# preamp.net
KiCad netlist of a schematic drawn in EAGLE
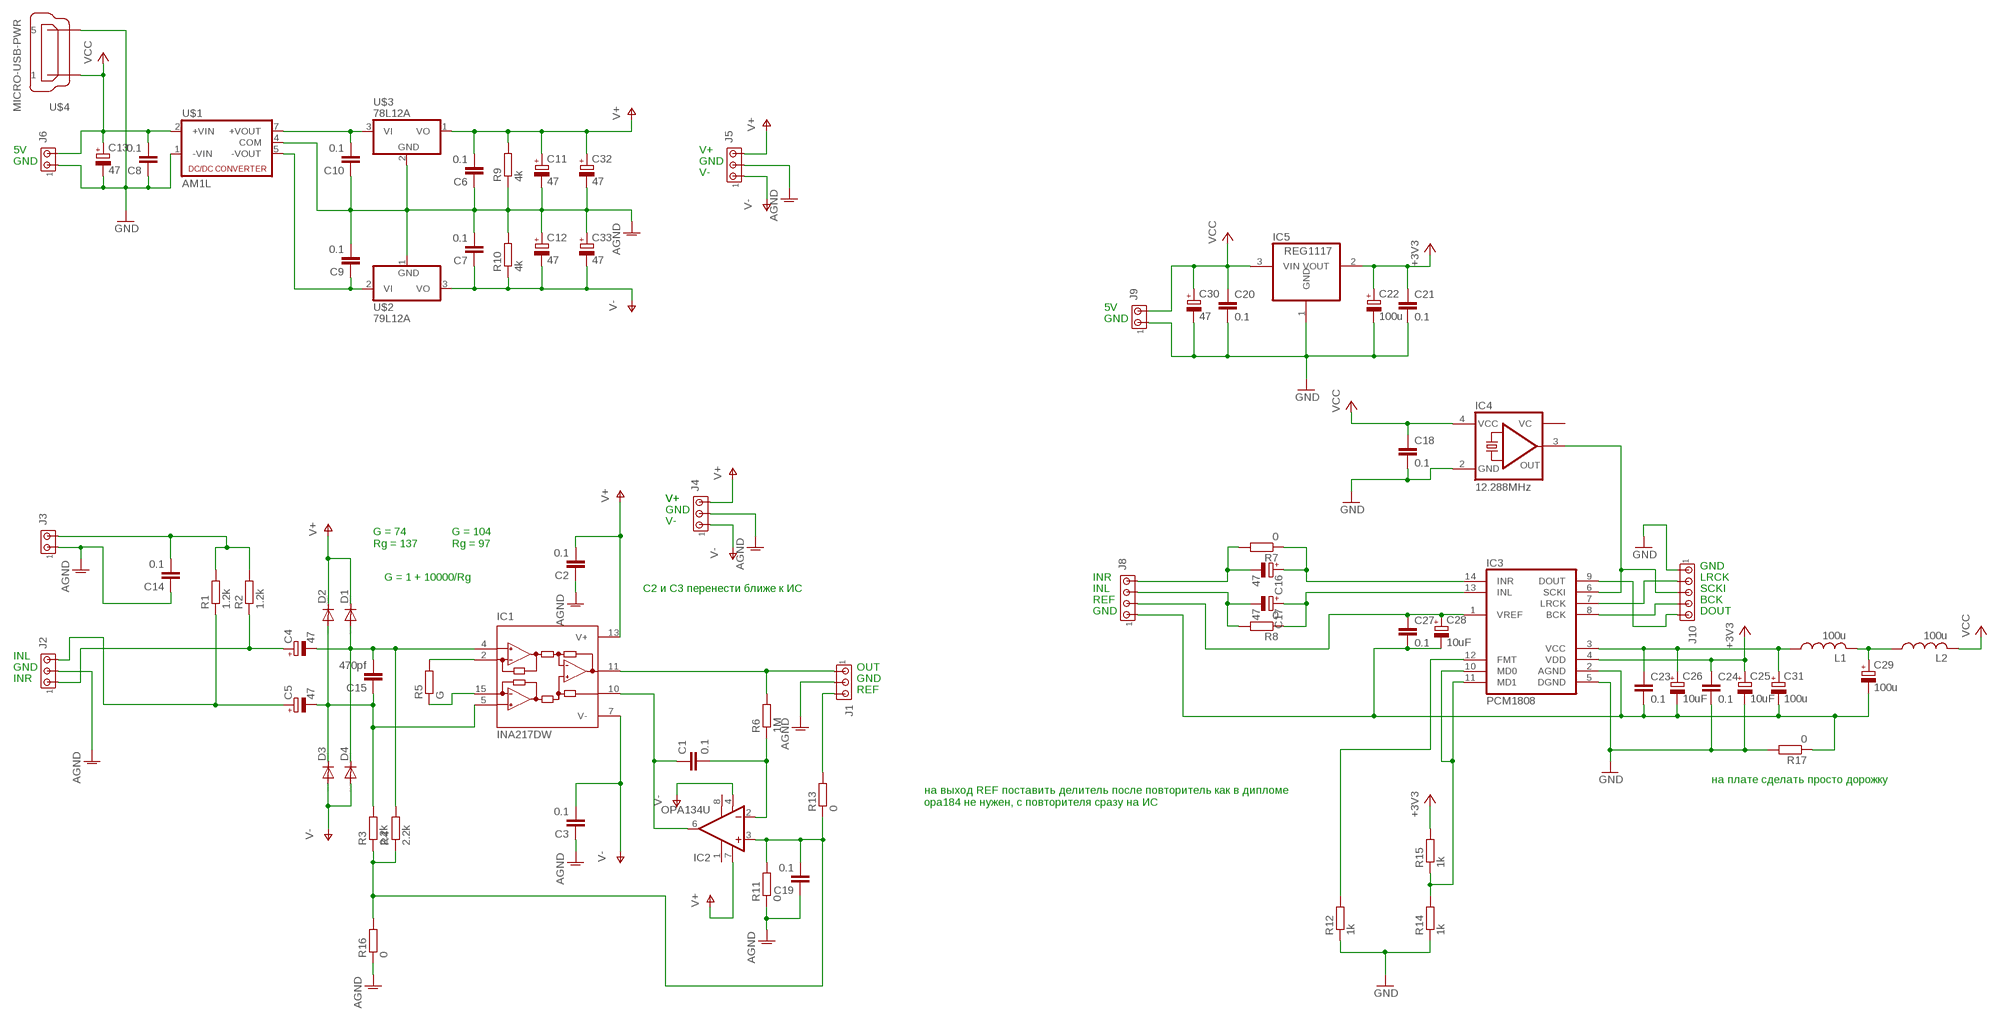
[diagram p0: schematic, sheet 1]

(export (version "E")
  (design (tool "Eeschema 10.0.6"))
  (components
    (comp (ref "C1")
      (value "0.1")
      (footprint "eagle-import:C0805")
      (libsource (lib "eagle-import") (part "C-EUC0805"))
    )
    (comp (ref "C2")
      (value "0.1")
      (footprint "eagle-import:C0805")
      (libsource (lib "eagle-import") (part "C-EUC0805"))
    )
    (comp (ref "C3")
      (value "0.1")
      (footprint "eagle-import:C0805")
      (libsource (lib "eagle-import") (part "C-EUC0805"))
    )
    (comp (ref "C4")
      (value "47")
      (footprint "eagle-import:153CLV-0605")
      (libsource (lib "eagle-import") (part "CPOL-EU153CLV-0605"))
    )
    (comp (ref "C5")
      (value "47")
      (footprint "eagle-import:153CLV-0605")
      (libsource (lib "eagle-import") (part "CPOL-EU153CLV-0605"))
    )
    (comp (ref "C6")
      (value "0.1")
      (footprint "eagle-import:C0805")
      (libsource (lib "eagle-import") (part "C-EUC0805"))
    )
    (comp (ref "C7")
      (value "0.1")
      (footprint "eagle-import:C0805")
      (libsource (lib "eagle-import") (part "C-EUC0805"))
    )
    (comp (ref "C8")
      (value "0.1")
      (footprint "eagle-import:C0805")
      (libsource (lib "eagle-import") (part "C-EUC0805"))
    )
    (comp (ref "C9")
      (value "0.1")
      (footprint "eagle-import:C0805")
      (libsource (lib "eagle-import") (part "C-EUC0805"))
    )
    (comp (ref "C10")
      (value "0.1")
      (footprint "eagle-import:C0805")
      (libsource (lib "eagle-import") (part "C-EUC0805"))
    )
    (comp (ref "C11")
      (value "47")
      (footprint "eagle-import:153CLV-0605")
      (libsource (lib "eagle-import") (part "CPOL-EU153CLV-0605"))
    )
    (comp (ref "C12")
      (value "47")
      (footprint "eagle-import:153CLV-0605")
      (libsource (lib "eagle-import") (part "CPOL-EU153CLV-0605"))
    )
    (comp (ref "C13")
      (value "47")
      (footprint "eagle-import:153CLV-0605")
      (libsource (lib "eagle-import") (part "CPOL-EU153CLV-0605"))
    )
    (comp (ref "C14")
      (value "0.1")
      (footprint "eagle-import:C0805")
      (libsource (lib "eagle-import") (part "C-EUC0805"))
    )
    (comp (ref "C15")
      (value "470pf")
      (footprint "eagle-import:C0805")
      (libsource (lib "eagle-import") (part "C-EUC0805"))
    )
    (comp (ref "C16")
      (value "47")
      (footprint "eagle-import:153CLV-0605")
      (libsource (lib "eagle-import") (part "CPOL-EU153CLV-0605"))
    )
    (comp (ref "C17")
      (value "47")
      (footprint "eagle-import:153CLV-0605")
      (libsource (lib "eagle-import") (part "CPOL-EU153CLV-0605"))
    )
    (comp (ref "C18")
      (value "0.1")
      (footprint "eagle-import:C0805")
      (libsource (lib "eagle-import") (part "C-EUC0805"))
    )
    (comp (ref "C19")
      (value "0.1")
      (footprint "eagle-import:C0805")
      (libsource (lib "eagle-import") (part "C-EUC0805"))
    )
    (comp (ref "C20")
      (value "0.1")
      (footprint "eagle-import:C0805")
      (libsource (lib "eagle-import") (part "C-EUC0805"))
    )
    (comp (ref "C21")
      (value "0.1")
      (footprint "eagle-import:C0805")
      (libsource (lib "eagle-import") (part "C-EUC0805"))
    )
    (comp (ref "C22")
      (value "100u")
      (footprint "eagle-import:153CLV-0605")
      (libsource (lib "eagle-import") (part "CPOL-EU153CLV-0605"))
    )
    (comp (ref "C23")
      (value "0.1")
      (footprint "eagle-import:C0805")
      (libsource (lib "eagle-import") (part "C-EUC0805"))
    )
    (comp (ref "C24")
      (value "0.1")
      (footprint "eagle-import:C0805")
      (libsource (lib "eagle-import") (part "C-EUC0805"))
    )
    (comp (ref "C25")
      (value "10uF")
      (footprint "eagle-import:SMC_A")
      (libsource (lib "eagle-import") (part "CPOL-EUSMCA"))
    )
    (comp (ref "C26")
      (value "10uF")
      (footprint "eagle-import:SMC_A")
      (libsource (lib "eagle-import") (part "CPOL-EUSMCA"))
    )
    (comp (ref "C27")
      (value "0.1")
      (footprint "eagle-import:C0805")
      (libsource (lib "eagle-import") (part "C-EUC0805"))
    )
    (comp (ref "C28")
      (value "10uF")
      (footprint "eagle-import:SMC_A")
      (libsource (lib "eagle-import") (part "CPOL-EUSMCA"))
    )
    (comp (ref "C29")
      (value "100u")
      (footprint "eagle-import:153CLV-0605")
      (libsource (lib "eagle-import") (part "CPOL-EU153CLV-0605"))
    )
    (comp (ref "C30")
      (value "47")
      (footprint "eagle-import:153CLV-0605")
      (libsource (lib "eagle-import") (part "CPOL-EU153CLV-0605"))
    )
    (comp (ref "C31")
      (value "100u")
      (footprint "eagle-import:153CLV-0605")
      (libsource (lib "eagle-import") (part "CPOL-EU153CLV-0605"))
    )
    (comp (ref "C32")
      (value "47")
      (footprint "eagle-import:153CLV-0605")
      (libsource (lib "eagle-import") (part "CPOL-EU153CLV-0605"))
    )
    (comp (ref "C33")
      (value "47")
      (footprint "eagle-import:153CLV-0605")
      (libsource (lib "eagle-import") (part "CPOL-EU153CLV-0605"))
    )
    (comp (ref "D1")
      (value "DIODE-SOD123")
      (footprint "eagle-import:SOD123")
      (libsource (lib "eagle-import") (part "DIODE-SOD123"))
    )
    (comp (ref "D2")
      (value "DIODE-SOD123")
      (footprint "eagle-import:SOD123")
      (libsource (lib "eagle-import") (part "DIODE-SOD123"))
    )
    (comp (ref "D3")
      (value "DIODE-SOD123")
      (footprint "eagle-import:SOD123")
      (libsource (lib "eagle-import") (part "DIODE-SOD123"))
    )
    (comp (ref "D4")
      (value "DIODE-SOD123")
      (footprint "eagle-import:SOD123")
      (libsource (lib "eagle-import") (part "DIODE-SOD123"))
    )
    (comp (ref "IC1")
      (value "INA217DW")
      (footprint "eagle-import:DW_RPDSO-G16")
      (fields (field (name "MF") "TEXAS INSTRUMENTS") (field (name "MPN") "INA217AIDWT"))
      (libsource (lib "eagle-import") (part "INA217DW"))
    )
    (comp (ref "IC2")
      (value "OPA134U")
      (footprint "eagle-import:SO08")
      (fields (field (name "MF") "TEXAS INSTRUMENTS") (field (name "MPN") "OPA134UA"))
      (libsource (lib "eagle-import") (part "OPA134U"))
    )
    (comp (ref "IC3")
      (value "PCM1808")
      (footprint "eagle-import:TSSOP14")
      (libsource (lib "eagle-import") (part "PCM1808"))
    )
    (comp (ref "IC4")
      (value "12.288MHz")
      (footprint "eagle-import:KXO-97")
      (libsource (lib "eagle-import") (part "KXO-97"))
    )
    (comp (ref "IC5")
      (value "REG1117")
      (footprint "eagle-import:SOT223")
      (libsource (lib "eagle-import") (part "REG1117"))
    )
    (comp (ref "J1")
      (value "MTA03-100")
      (footprint "eagle-import:10X03MTA")
      (libsource (lib "eagle-import") (part "MTA03-100"))
    )
    (comp (ref "J2")
      (value "MTA03-100")
      (footprint "eagle-import:10X03MTA")
      (libsource (lib "eagle-import") (part "MTA03-100"))
    )
    (comp (ref "J3")
      (value "MTA02-100")
      (footprint "eagle-import:10X02MTA")
      (libsource (lib "eagle-import") (part "MTA02-100"))
    )
    (comp (ref "J4")
      (value "MTA03-100")
      (footprint "eagle-import:10X03MTA")
      (libsource (lib "eagle-import") (part "MTA03-100"))
    )
    (comp (ref "J5")
      (value "MTA03-100")
      (footprint "eagle-import:10X03MTA")
      (libsource (lib "eagle-import") (part "MTA03-100"))
    )
    (comp (ref "J6")
      (value "MTA02-100")
      (footprint "eagle-import:10X02MTA")
      (libsource (lib "eagle-import") (part "MTA02-100"))
    )
    (comp (ref "J8")
      (value "MTA04-100")
      (footprint "eagle-import:10X04MTA")
      (libsource (lib "eagle-import") (part "MTA04-100"))
    )
    (comp (ref "J9")
      (value "MTA02-100")
      (footprint "eagle-import:10X02MTA")
      (libsource (lib "eagle-import") (part "MTA02-100"))
    )
    (comp (ref "J10")
      (value "MTA05-100")
      (footprint "eagle-import:10X05MTA")
      (libsource (lib "eagle-import") (part "MTA05-100"))
    )
    (comp (ref "L1")
      (value "100u")
      (footprint "eagle-import:L3225M")
      (libsource (lib "eagle-import") (part "L-USL3225M"))
    )
    (comp (ref "L2")
      (value "100u")
      (footprint "eagle-import:L3225M")
      (libsource (lib "eagle-import") (part "L-USL3225M"))
    )
    (comp (ref "R1")
      (value "1.2k")
      (footprint "eagle-import:R0805")
      (libsource (lib "eagle-import") (part "R-EU_R0805"))
    )
    (comp (ref "R2")
      (value "1.2k")
      (footprint "eagle-import:R0805")
      (libsource (lib "eagle-import") (part "R-EU_R0805"))
    )
    (comp (ref "R3")
      (value "2.2k")
      (footprint "eagle-import:R0805")
      (libsource (lib "eagle-import") (part "R-EU_R0805"))
    )
    (comp (ref "R4")
      (value "2.2k")
      (footprint "eagle-import:R0805")
      (libsource (lib "eagle-import") (part "R-EU_R0805"))
    )
    (comp (ref "R5")
      (value "G")
      (footprint "eagle-import:R0805")
      (libsource (lib "eagle-import") (part "R-EU_R0805"))
    )
    (comp (ref "R6")
      (value "1M")
      (footprint "eagle-import:R0805")
      (libsource (lib "eagle-import") (part "R-EU_R0805"))
    )
    (comp (ref "R7")
      (value "0")
      (footprint "eagle-import:R0805")
      (libsource (lib "eagle-import") (part "R-EU_R0805"))
    )
    (comp (ref "R8")
      (value "0")
      (footprint "eagle-import:R0805")
      (libsource (lib "eagle-import") (part "R-EU_R0805"))
    )
    (comp (ref "R9")
      (value "4k")
      (footprint "eagle-import:R0805")
      (libsource (lib "eagle-import") (part "R-EU_R0805"))
    )
    (comp (ref "R10")
      (value "4k")
      (footprint "eagle-import:R0805")
      (libsource (lib "eagle-import") (part "R-EU_R0805"))
    )
    (comp (ref "R11")
      (value "0")
      (footprint "eagle-import:R0805")
      (libsource (lib "eagle-import") (part "R-EU_R0805"))
    )
    (comp (ref "R12")
      (value "1k")
      (footprint "eagle-import:R0805")
      (libsource (lib "eagle-import") (part "R-EU_R0805"))
    )
    (comp (ref "R13")
      (value "0")
      (footprint "eagle-import:R0805")
      (libsource (lib "eagle-import") (part "R-EU_R0805"))
    )
    (comp (ref "R14")
      (value "1k")
      (footprint "eagle-import:R0805")
      (libsource (lib "eagle-import") (part "R-EU_R0805"))
    )
    (comp (ref "R15")
      (value "1k")
      (footprint "eagle-import:R0805")
      (libsource (lib "eagle-import") (part "R-EU_R0805"))
    )
    (comp (ref "R16")
      (value "0")
      (footprint "eagle-import:R0805")
      (libsource (lib "eagle-import") (part "R-EU_R0805"))
    )
    (comp (ref "R17")
      (value "0")
      (footprint "eagle-import:R0805")
      (libsource (lib "eagle-import") (part "R-EU_R0805"))
    )
    (comp (ref "U$1")
      (value "AM1L")
      (footprint "eagle-import:SO20")
      (libsource (lib "eagle-import") (part "AM1L"))
    )
    (comp (ref "U$2")
      (value "79L12A")
      (footprint "eagle-import:SOT89")
      (libsource (lib "eagle-import") (part "79L12A"))
    )
    (comp (ref "U$3")
      (value "78L12A")
      (footprint "eagle-import:SOT89")
      (libsource (lib "eagle-import") (part "78L12A"))
    )
    (comp (ref "U$4")
      (value "MICRO-USB-PWR")
      (footprint "eagle-import:MICRO-USB")
      (libsource (lib "eagle-import") (part "MICRO-USB-PWR"))
    )
  )
  (nets
    (net (code "1") (name "+3V3") (class "Default")
      (node (ref "C21") (pin "1") (pinfunction "1_1") (pintype "passive"))
      (node (ref "C22") (pin "+") (pinfunction "+_+") (pintype "passive"))
      (node (ref "C24") (pin "1") (pinfunction "1_1") (pintype "passive"))
      (node (ref "C25") (pin "+") (pinfunction "+_+") (pintype "passive"))
      (node (ref "IC3") (pin "4") (pinfunction "VDD_4") (pintype "power_in"))
      (node (ref "IC5") (pin "2") (pinfunction "VOUT_2") (pintype "output"))
      (node (ref "R15") (pin "2") (pinfunction "2_2") (pintype "passive"))
    )
    (net (code "2") (name "AGND") (class "Default")
      (node (ref "C10") (pin "1") (pinfunction "1_1") (pintype "passive"))
      (node (ref "C11") (pin "-") (pinfunction "-_-") (pintype "passive"))
      (node (ref "C12") (pin "+") (pinfunction "+_+") (pintype "passive"))
      (node (ref "C14") (pin "1") (pinfunction "1_1") (pintype "passive"))
      (node (ref "C19") (pin "1") (pinfunction "1_1") (pintype "passive"))
      (node (ref "C2") (pin "1") (pinfunction "1_1") (pintype "passive"))
      (node (ref "C3") (pin "1") (pinfunction "1_1") (pintype "passive"))
      (node (ref "C32") (pin "-") (pinfunction "-_-") (pintype "passive"))
      (node (ref "C33") (pin "+") (pinfunction "+_+") (pintype "passive"))
      (node (ref "C6") (pin "1") (pinfunction "1_1") (pintype "passive"))
      (node (ref "C7") (pin "2") (pinfunction "2_2") (pintype "passive"))
      (node (ref "C9") (pin "2") (pinfunction "2_2") (pintype "passive"))
      (node (ref "J1") (pin "2") (pinfunction "2_2") (pintype "passive"))
      (node (ref "J2") (pin "2") (pinfunction "2_2") (pintype "passive"))
      (node (ref "J3") (pin "1") (pinfunction "1_1") (pintype "passive"))
      (node (ref "J4") (pin "2") (pinfunction "2_2") (pintype "passive"))
      (node (ref "J5") (pin "2") (pinfunction "2_2") (pintype "passive"))
      (node (ref "R10") (pin "2") (pinfunction "2_2") (pintype "passive"))
      (node (ref "R11") (pin "1") (pinfunction "1_1") (pintype "passive"))
      (node (ref "R16") (pin "1") (pinfunction "1_1") (pintype "passive"))
      (node (ref "R9") (pin "1") (pinfunction "1_1") (pintype "passive"))
      (node (ref "U$1") (pin "4") (pinfunction "COM_4") (pintype "passive"))
      (node (ref "U$2") (pin "1") (pinfunction "GND_1") (pintype "passive"))
      (node (ref "U$3") (pin "2") (pinfunction "GND_2") (pintype "passive"))
    )
    (net (code "3") (name "GND") (class "Default")
      (node (ref "C13") (pin "-") (pinfunction "-_-") (pintype "passive"))
      (node (ref "C18") (pin "2") (pinfunction "2_2") (pintype "passive"))
      (node (ref "C20") (pin "2") (pinfunction "2_2") (pintype "passive"))
      (node (ref "C21") (pin "2") (pinfunction "2_2") (pintype "passive"))
      (node (ref "C22") (pin "-") (pinfunction "-_-") (pintype "passive"))
      (node (ref "C24") (pin "2") (pinfunction "2_2") (pintype "passive"))
      (node (ref "C25") (pin "-") (pinfunction "-_-") (pintype "passive"))
      (node (ref "C30") (pin "-") (pinfunction "-_-") (pintype "passive"))
      (node (ref "C8") (pin "1") (pinfunction "1_1") (pintype "passive"))
      (node (ref "IC3") (pin "5") (pinfunction "DGND_5") (pintype "power_in"))
      (node (ref "IC4") (pin "2") (pinfunction "GND_2") (pintype "power_in"))
      (node (ref "IC5") (pin "1") (pinfunction "GND_1") (pintype "power_in"))
      (node (ref "J10") (pin "1") (pinfunction "1_1") (pintype "passive"))
      (node (ref "J6") (pin "1") (pinfunction "1_1") (pintype "passive"))
      (node (ref "J9") (pin "1") (pinfunction "1_1") (pintype "passive"))
      (node (ref "R12") (pin "1") (pinfunction "1_1") (pintype "passive"))
      (node (ref "R14") (pin "1") (pinfunction "1_1") (pintype "passive"))
      (node (ref "R17") (pin "2") (pinfunction "2_2") (pintype "passive"))
      (node (ref "U$1") (pin "1") (pinfunction "-VIN_1") (pintype "passive"))
      (node (ref "U$4") (pin "5") (pinfunction "5_5") (pintype "passive"))
    )
    (net (code "4") (name "Net-(C4-Pad+)") (class "Default")
      (node (ref "C4") (pin "+") (pinfunction "+_+") (pintype "passive"))
      (node (ref "J2") (pin "1") (pinfunction "1_1") (pintype "passive"))
      (node (ref "R2") (pin "1") (pinfunction "1_1") (pintype "passive"))
    )
    (net (code "5") (name "Net-(C5-Pad+)") (class "Default")
      (node (ref "C5") (pin "+") (pinfunction "+_+") (pintype "passive"))
      (node (ref "J2") (pin "3") (pinfunction "3_3") (pintype "passive"))
      (node (ref "R1") (pin "1") (pinfunction "1_1") (pintype "passive"))
    )
    (net (code "6") (name "Net-(C14-Pad2)") (class "Default")
      (node (ref "C14") (pin "2") (pinfunction "2_2") (pintype "passive"))
      (node (ref "J3") (pin "2") (pinfunction "2_2") (pintype "passive"))
      (node (ref "R1") (pin "2") (pinfunction "2_2") (pintype "passive"))
      (node (ref "R2") (pin "2") (pinfunction "2_2") (pintype "passive"))
    )
    (net (code "7") (name "Net-(C16-Pad-)") (class "Default")
      (node (ref "C16") (pin "-") (pinfunction "-_-") (pintype "passive"))
      (node (ref "J8") (pin "4") (pinfunction "4_4") (pintype "passive"))
      (node (ref "R7") (pin "2") (pinfunction "2_2") (pintype "passive"))
    )
    (net (code "8") (name "Net-(C17-Pad-)") (class "Default")
      (node (ref "C17") (pin "-") (pinfunction "-_-") (pintype "passive"))
      (node (ref "J8") (pin "3") (pinfunction "3_3") (pintype "passive"))
      (node (ref "R8") (pin "2") (pinfunction "2_2") (pintype "passive"))
    )
    (net (code "9") (name "Net-(C29-Pad+)") (class "Default")
      (node (ref "C29") (pin "+") (pinfunction "+_+") (pintype "passive"))
      (node (ref "L1") (pin "2") (pinfunction "2_2") (pintype "passive"))
      (node (ref "L2") (pin "1") (pinfunction "1_1") (pintype "passive"))
    )
    (net (code "10") (name "Net-(IC1-+IN)") (class "Default")
      (node (ref "C15") (pin "1") (pinfunction "1_1") (pintype "passive"))
      (node (ref "C5") (pin "-") (pinfunction "-_-") (pintype "passive"))
      (node (ref "D2") (pin "A") (pinfunction "A_A") (pintype "passive"))
      (node (ref "D3") (pin "C") (pinfunction "C_C") (pintype "passive"))
      (node (ref "IC1") (pin "5") (pinfunction "+IN_5") (pintype "input"))
      (node (ref "R3") (pin "2") (pinfunction "2_2") (pintype "passive"))
    )
    (net (code "11") (name "Net-(IC1--IN)") (class "Default")
      (node (ref "C15") (pin "2") (pinfunction "2_2") (pintype "passive"))
      (node (ref "C4") (pin "-") (pinfunction "-_-") (pintype "passive"))
      (node (ref "D1") (pin "A") (pinfunction "A_A") (pintype "passive"))
      (node (ref "D4") (pin "C") (pinfunction "C_C") (pintype "passive"))
      (node (ref "IC1") (pin "4") (pinfunction "-IN_4") (pintype "input"))
      (node (ref "R4") (pin "2") (pinfunction "2_2") (pintype "passive"))
    )
    (net (code "12") (name "Net-(IC1-OUT)") (class "Default")
      (node (ref "IC1") (pin "11") (pinfunction "OUT_11") (pintype "output"))
      (node (ref "J1") (pin "1") (pinfunction "1_1") (pintype "passive"))
      (node (ref "R6") (pin "2") (pinfunction "2_2") (pintype "passive"))
    )
    (net (code "13") (name "Net-(IC1-REF)") (class "Default")
      (node (ref "C1") (pin "1") (pinfunction "1_1") (pintype "passive"))
      (node (ref "IC1") (pin "10") (pinfunction "REF_10") (pintype "passive"))
      (node (ref "IC2") (pin "6") (pinfunction "OUT_6") (pintype "output"))
    )
    (net (code "14") (name "Net-(IC1-RG1)") (class "Default")
      (node (ref "IC1") (pin "2") (pinfunction "RG1_2") (pintype "passive"))
      (node (ref "R5") (pin "2") (pinfunction "2_2") (pintype "passive"))
    )
    (net (code "15") (name "Net-(IC1-RG2)") (class "Default")
      (node (ref "IC1") (pin "15") (pinfunction "RG2_15") (pintype "passive"))
      (node (ref "R5") (pin "1") (pinfunction "1_1") (pintype "passive"))
    )
    (net (code "16") (name "Net-(IC2-+IN)") (class "Default")
      (node (ref "C19") (pin "2") (pinfunction "2_2") (pintype "passive"))
      (node (ref "IC2") (pin "3") (pinfunction "+IN_3") (pintype "input"))
      (node (ref "R11") (pin "2") (pinfunction "2_2") (pintype "passive"))
      (node (ref "R13") (pin "1") (pinfunction "1_1") (pintype "passive"))
      (node (ref "R16") (pin "2") (pinfunction "2_2") (pintype "passive"))
      (node (ref "R3") (pin "1") (pinfunction "1_1") (pintype "passive"))
      (node (ref "R4") (pin "1") (pinfunction "1_1") (pintype "passive"))
    )
    (net (code "17") (name "Net-(IC2--IN)") (class "Default")
      (node (ref "C1") (pin "2") (pinfunction "2_2") (pintype "passive"))
      (node (ref "IC2") (pin "2") (pinfunction "-IN_2") (pintype "input"))
      (node (ref "R6") (pin "1") (pinfunction "1_1") (pintype "passive"))
    )
    (net (code "18") (name "Net-(IC3-AGND)") (class "Default")
      (node (ref "C23") (pin "2") (pinfunction "2_2") (pintype "passive"))
      (node (ref "C26") (pin "-") (pinfunction "-_-") (pintype "passive"))
      (node (ref "C27") (pin "2") (pinfunction "2_2") (pintype "passive"))
      (node (ref "C28") (pin "-") (pinfunction "-_-") (pintype "passive"))
      (node (ref "C29") (pin "-") (pinfunction "-_-") (pintype "passive"))
      (node (ref "C31") (pin "-") (pinfunction "-_-") (pintype "passive"))
      (node (ref "IC3") (pin "2") (pinfunction "AGND_2") (pintype "power_in"))
      (node (ref "J8") (pin "1") (pinfunction "1_1") (pintype "passive"))
      (node (ref "R17") (pin "1") (pinfunction "1_1") (pintype "passive"))
    )
    (net (code "19") (name "Net-(IC3-BCK)") (class "Default")
      (node (ref "IC3") (pin "8") (pinfunction "BCK_8") (pintype "bidirectional"))
      (node (ref "J10") (pin "4") (pinfunction "4_4") (pintype "passive"))
    )
    (net (code "20") (name "Net-(IC3-DOUT)") (class "Default")
      (node (ref "IC3") (pin "9") (pinfunction "DOUT_9") (pintype "output"))
      (node (ref "J10") (pin "5") (pinfunction "5_5") (pintype "passive"))
    )
    (net (code "21") (name "Net-(IC3-FMT)") (class "Default")
      (node (ref "IC3") (pin "12") (pinfunction "FMT_12") (pintype "input"))
      (node (ref "R12") (pin "2") (pinfunction "2_2") (pintype "passive"))
    )
    (net (code "22") (name "Net-(IC3-INL)") (class "Default")
      (node (ref "C17") (pin "+") (pinfunction "+_+") (pintype "passive"))
      (node (ref "IC3") (pin "13") (pinfunction "INL_13") (pintype "input"))
      (node (ref "R8") (pin "1") (pinfunction "1_1") (pintype "passive"))
    )
    (net (code "23") (name "Net-(IC3-INR)") (class "Default")
      (node (ref "C16") (pin "+") (pinfunction "+_+") (pintype "passive"))
      (node (ref "IC3") (pin "14") (pinfunction "INR_14") (pintype "input"))
      (node (ref "R7") (pin "1") (pinfunction "1_1") (pintype "passive"))
    )
    (net (code "24") (name "Net-(IC3-LRCK)") (class "Default")
      (node (ref "IC3") (pin "7") (pinfunction "LRCK_7") (pintype "bidirectional"))
      (node (ref "J10") (pin "2") (pinfunction "2_2") (pintype "passive"))
    )
    (net (code "25") (name "Net-(IC3-MD0)") (class "Default")
      (node (ref "IC3") (pin "10") (pinfunction "MD0_10") (pintype "input"))
      (node (ref "IC3") (pin "11") (pinfunction "MD1_11") (pintype "input"))
      (node (ref "R14") (pin "2") (pinfunction "2_2") (pintype "passive"))
      (node (ref "R15") (pin "1") (pinfunction "1_1") (pintype "passive"))
    )
    (net (code "26") (name "Net-(IC3-SCKI)") (class "Default")
      (node (ref "IC3") (pin "6") (pinfunction "SCKI_6") (pintype "bidirectional"))
      (node (ref "IC4") (pin "3") (pinfunction "OUT_3") (pintype "output"))
      (node (ref "J10") (pin "3") (pinfunction "3_3") (pintype "passive"))
    )
    (net (code "27") (name "Net-(IC3-VCC)") (class "Default")
      (node (ref "C23") (pin "1") (pinfunction "1_1") (pintype "passive"))
      (node (ref "C26") (pin "+") (pinfunction "+_+") (pintype "passive"))
      (node (ref "C31") (pin "+") (pinfunction "+_+") (pintype "passive"))
      (node (ref "IC3") (pin "3") (pinfunction "VCC_3") (pintype "power_in"))
      (node (ref "L1") (pin "1") (pinfunction "1_1") (pintype "passive"))
    )
    (net (code "28") (name "Net-(IC3-VREF)") (class "Default")
      (node (ref "C27") (pin "1") (pinfunction "1_1") (pintype "passive"))
      (node (ref "C28") (pin "+") (pinfunction "+_+") (pintype "passive"))
      (node (ref "IC3") (pin "1") (pinfunction "VREF_1") (pintype "passive"))
      (node (ref "J8") (pin "2") (pinfunction "2_2") (pintype "passive"))
    )
    (net (code "29") (name "Net-(J1-Pad3)") (class "Default")
      (node (ref "J1") (pin "3") (pinfunction "3_3") (pintype "passive"))
      (node (ref "R13") (pin "2") (pinfunction "2_2") (pintype "passive"))
    )
    (net (code "30") (name "Net-(U$1-+VOUT)") (class "Default")
      (node (ref "C10") (pin "2") (pinfunction "2_2") (pintype "passive"))
      (node (ref "U$1") (pin "7") (pinfunction "+VOUT_7") (pintype "passive"))
      (node (ref "U$3") (pin "3") (pinfunction "VI_3") (pintype "input"))
    )
    (net (code "31") (name "Net-(U$1--VOUT)") (class "Default")
      (node (ref "C9") (pin "1") (pinfunction "1_1") (pintype "passive"))
      (node (ref "U$1") (pin "5") (pinfunction "-VOUT_5") (pintype "passive"))
      (node (ref "U$2") (pin "2") (pinfunction "VI_2") (pintype "input"))
    )
    (net (code "32") (name "V+") (class "Default")
      (node (ref "C11") (pin "+") (pinfunction "+_+") (pintype "passive"))
      (node (ref "C2") (pin "2") (pinfunction "2_2") (pintype "passive"))
      (node (ref "C32") (pin "+") (pinfunction "+_+") (pintype "passive"))
      (node (ref "C6") (pin "2") (pinfunction "2_2") (pintype "passive"))
      (node (ref "D1") (pin "C") (pinfunction "C_C") (pintype "passive"))
      (node (ref "D2") (pin "C") (pinfunction "C_C") (pintype "passive"))
      (node (ref "IC1") (pin "13") (pinfunction "V+_13") (pintype "power_in"))
      (node (ref "IC2") (pin "7") (pinfunction "V+_7") (pintype "power_in"))
      (node (ref "J4") (pin "3") (pinfunction "3_3") (pintype "passive"))
      (node (ref "J5") (pin "3") (pinfunction "3_3") (pintype "passive"))
      (node (ref "R9") (pin "2") (pinfunction "2_2") (pintype "passive"))
      (node (ref "U$3") (pin "1") (pinfunction "VO_1") (pintype "passive"))
    )
    (net (code "33") (name "V-") (class "Default")
      (node (ref "C12") (pin "-") (pinfunction "-_-") (pintype "passive"))
      (node (ref "C3") (pin "2") (pinfunction "2_2") (pintype "passive"))
      (node (ref "C33") (pin "-") (pinfunction "-_-") (pintype "passive"))
      (node (ref "C7") (pin "1") (pinfunction "1_1") (pintype "passive"))
      (node (ref "D3") (pin "A") (pinfunction "A_A") (pintype "passive"))
      (node (ref "D4") (pin "A") (pinfunction "A_A") (pintype "passive"))
      (node (ref "IC1") (pin "7") (pinfunction "V-_7") (pintype "power_in"))
      (node (ref "IC2") (pin "4") (pinfunction "V-_4") (pintype "power_in"))
      (node (ref "J4") (pin "1") (pinfunction "1_1") (pintype "passive"))
      (node (ref "J5") (pin "1") (pinfunction "1_1") (pintype "passive"))
      (node (ref "R10") (pin "1") (pinfunction "1_1") (pintype "passive"))
      (node (ref "U$2") (pin "3") (pinfunction "VO_3") (pintype "passive"))
    )
    (net (code "34") (name "VCC") (class "Default")
      (node (ref "C13") (pin "+") (pinfunction "+_+") (pintype "passive"))
      (node (ref "C18") (pin "1") (pinfunction "1_1") (pintype "passive"))
      (node (ref "C20") (pin "1") (pinfunction "1_1") (pintype "passive"))
      (node (ref "C30") (pin "+") (pinfunction "+_+") (pintype "passive"))
      (node (ref "C8") (pin "2") (pinfunction "2_2") (pintype "passive"))
      (node (ref "IC4") (pin "4") (pinfunction "VCC_4") (pintype "power_in"))
      (node (ref "IC5") (pin "3") (pinfunction "VIN_3") (pintype "input"))
      (node (ref "J6") (pin "2") (pinfunction "2_2") (pintype "passive"))
      (node (ref "J9") (pin "2") (pinfunction "2_2") (pintype "passive"))
      (node (ref "L2") (pin "2") (pinfunction "2_2") (pintype "passive"))
      (node (ref "U$1") (pin "2") (pinfunction "+VIN_2") (pintype "passive"))
      (node (ref "U$4") (pin "1") (pinfunction "1_1") (pintype "passive"))
    )
    (net (code "35") (name "unconnected-(IC2-TRIM1-Pad1)") (class "Default")
      (node (ref "IC2") (pin "1") (pinfunction "TRIM1_1") (pintype "passive"))
    )
    (net (code "36") (name "unconnected-(IC2-TRIM2-Pad8)") (class "Default")
      (node (ref "IC2") (pin "8") (pinfunction "TRIM2_8") (pintype "passive"))
    )
    (net (code "37") (name "unconnected-(IC4-VC-Pad1)") (class "Default")
      (node (ref "IC4") (pin "1") (pinfunction "VC_1") (pintype "input"))
    )
  )
)
